# iv-17single.net
KiCad netlist of a schematic drawn in EAGLE
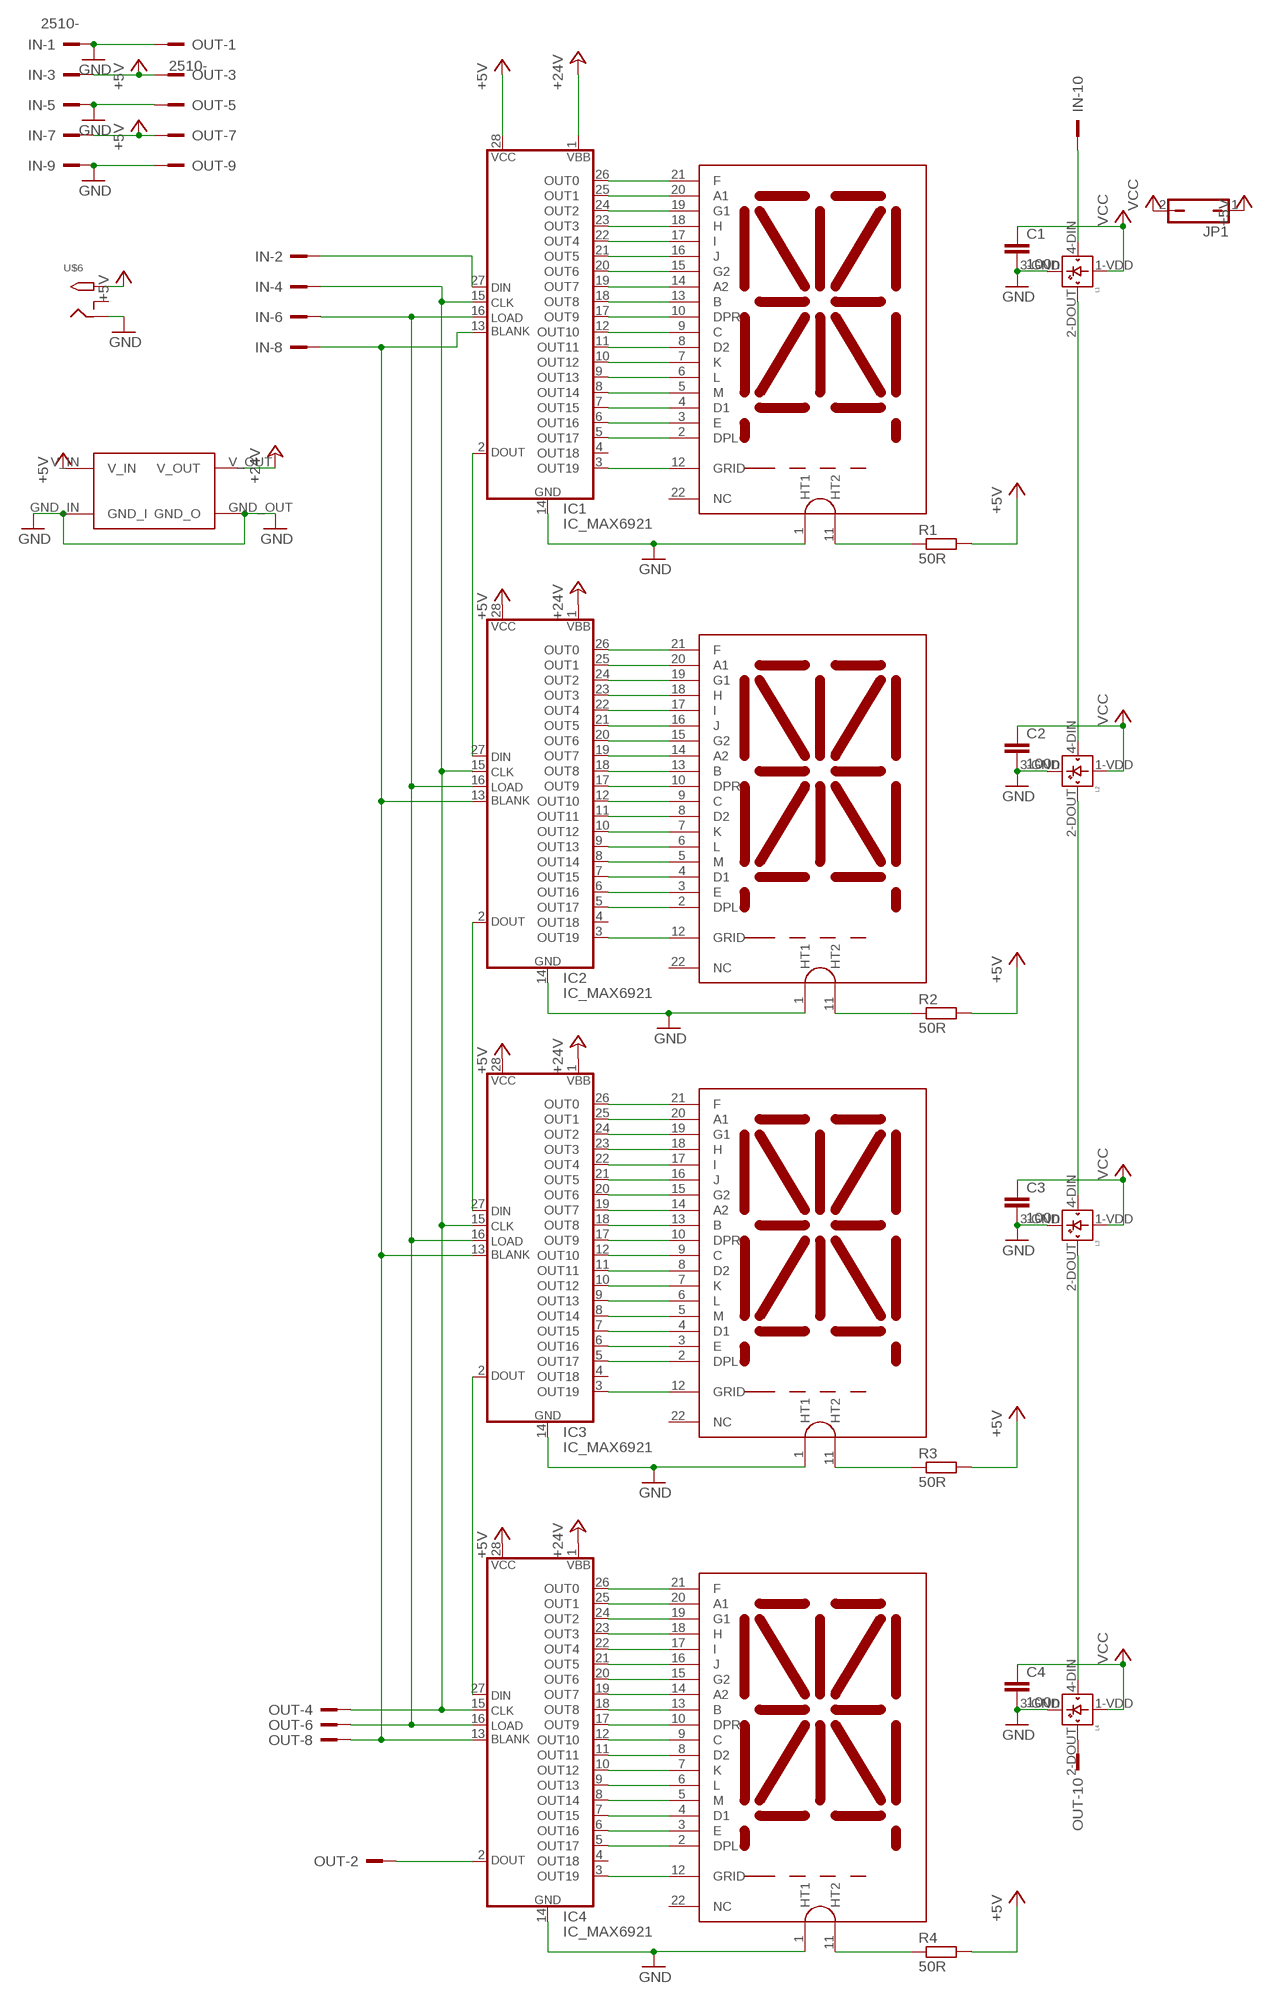
[diagram p0: schematic, sheet 1]

(export (version "E")
  (design (tool "Eeschema 10.0.6"))
  (components
    (comp (ref "1")
      (value "IV-17_DISPIV-17")
      (footprint "eagle-import:IV-17")
      (libsource (lib "eagle-import") (part "IV-17_DISPIV-17"))
    )
    (comp (ref "2")
      (value "IV-17_DISPIV-17")
      (footprint "eagle-import:IV-17")
      (libsource (lib "eagle-import") (part "IV-17_DISPIV-17"))
    )
    (comp (ref "3")
      (value "IV-17_DISPIV-17")
      (footprint "eagle-import:IV-17")
      (libsource (lib "eagle-import") (part "IV-17_DISPIV-17"))
    )
    (comp (ref "4")
      (value "IV-17_DISPIV-17")
      (footprint "eagle-import:IV-17")
      (libsource (lib "eagle-import") (part "IV-17_DISPIV-17"))
    )
    (comp (ref "C1")
      (value "100n")
      (footprint "eagle-import:C0805")
      (libsource (lib "eagle-import") (part "C-EUC0805"))
    )
    (comp (ref "C2")
      (value "100n")
      (footprint "eagle-import:C0805")
      (libsource (lib "eagle-import") (part "C-EUC0805"))
    )
    (comp (ref "C3")
      (value "100n")
      (footprint "eagle-import:C0805")
      (libsource (lib "eagle-import") (part "C-EUC0805"))
    )
    (comp (ref "C4")
      (value "100n")
      (footprint "eagle-import:C0805")
      (libsource (lib "eagle-import") (part "C-EUC0805"))
    )
    (comp (ref "IC1")
      (value "IC_MAX6921")
      (footprint "eagle-import:S28")
      (libsource (lib "eagle-import") (part "IC_MAX6921"))
    )
    (comp (ref "IC2")
      (value "IC_MAX6921")
      (footprint "eagle-import:S28")
      (libsource (lib "eagle-import") (part "IC_MAX6921"))
    )
    (comp (ref "IC3")
      (value "IC_MAX6921")
      (footprint "eagle-import:S28")
      (libsource (lib "eagle-import") (part "IC_MAX6921"))
    )
    (comp (ref "IC4")
      (value "IC_MAX6921")
      (footprint "eagle-import:S28")
      (libsource (lib "eagle-import") (part "IC_MAX6921"))
    )
    (comp (ref "IN")
      (value "2510-")
      (footprint "eagle-import:PAK100_2500-10")
      (fields (field (name "MF") "3M") (field (name "MPN") "2510-6002UB"))
      (libsource (lib "eagle-import") (part "2510-"))
    )
    (comp (ref "JP1")
      (value "JP1Q")
      (footprint "eagle-import:JP1")
      (libsource (lib "eagle-import") (part "JP1Q"))
    )
    (comp (ref "L1")
      (value "WS2812B")
      (footprint "eagle-import:WS2812B")
      (libsource (lib "eagle-import") (part "WS2812B"))
    )
    (comp (ref "L2")
      (value "WS2812B")
      (footprint "eagle-import:WS2812B")
      (libsource (lib "eagle-import") (part "WS2812B"))
    )
    (comp (ref "L3")
      (value "WS2812B")
      (footprint "eagle-import:WS2812B")
      (libsource (lib "eagle-import") (part "WS2812B"))
    )
    (comp (ref "L4")
      (value "WS2812B")
      (footprint "eagle-import:WS2812B")
      (libsource (lib "eagle-import") (part "WS2812B"))
    )
    (comp (ref "OUT")
      (value "2510-")
      (footprint "eagle-import:PAK100_2500-10")
      (fields (field (name "MF") "3M") (field (name "MPN") "2510-6002UB"))
      (libsource (lib "eagle-import") (part "2510-"))
    )
    (comp (ref "R1")
      (value "50R")
      (footprint "eagle-import:0207_10")
      (libsource (lib "eagle-import") (part "R-EU_0207/10"))
    )
    (comp (ref "R2")
      (value "50R")
      (footprint "eagle-import:0207_10")
      (libsource (lib "eagle-import") (part "R-EU_0207/10"))
    )
    (comp (ref "R3")
      (value "50R")
      (footprint "eagle-import:0207_10")
      (libsource (lib "eagle-import") (part "R-EU_0207/10"))
    )
    (comp (ref "R4")
      (value "50R")
      (footprint "eagle-import:0207_10")
      (libsource (lib "eagle-import") (part "R-EU_0207/10"))
    )
    (comp (ref "U$5")
      (value "STEP_UP_MODULE")
      (footprint "eagle-import:STEP_UP_MODULE")
      (libsource (lib "eagle-import") (part "STEP_UP_MODULE"))
    )
    (comp (ref "U$6")
      (value "2.1MMJACKTHM")
      (footprint "eagle-import:PJ-102A")
      (libsource (lib "eagle-import") (part "2.1MMJACKTHM"))
    )
  )
  (nets
    (net (code "1") (name "+5V") (class "Default")
      (node (ref "IC1") (pin "28") (pinfunction "VCC_28") (pintype "power_in"))
      (node (ref "IC2") (pin "28") (pinfunction "VCC_28") (pintype "power_in"))
      (node (ref "IC3") (pin "28") (pinfunction "VCC_28") (pintype "power_in"))
      (node (ref "IC4") (pin "28") (pinfunction "VCC_28") (pintype "power_in"))
      (node (ref "IN") (pin "3") (pinfunction "KL_3") (pintype "passive"))
      (node (ref "IN") (pin "7") (pinfunction "KL_7") (pintype "passive"))
      (node (ref "JP1") (pin "1") (pinfunction "1_1") (pintype "passive"))
      (node (ref "OUT") (pin "3") (pinfunction "KL_3") (pintype "passive"))
      (node (ref "OUT") (pin "7") (pinfunction "KL_7") (pintype "passive"))
      (node (ref "R1") (pin "2") (pinfunction "2_2") (pintype "passive"))
      (node (ref "R2") (pin "2") (pinfunction "2_2") (pintype "passive"))
      (node (ref "R3") (pin "2") (pinfunction "2_2") (pintype "passive"))
      (node (ref "R4") (pin "2") (pinfunction "2_2") (pintype "passive"))
      (node (ref "U$5") (pin "V_IN") (pinfunction "V_IN_V_IN") (pintype "power_in"))
      (node (ref "U$6") (pin "TIP") (pinfunction "TIP_TIP") (pintype "bidirectional"))
    )
    (net (code "2") (name "+24V") (class "Default")
      (node (ref "IC1") (pin "1") (pinfunction "VBB_1") (pintype "power_in"))
      (node (ref "IC2") (pin "1") (pinfunction "VBB_1") (pintype "power_in"))
      (node (ref "IC3") (pin "1") (pinfunction "VBB_1") (pintype "power_in"))
      (node (ref "IC4") (pin "1") (pinfunction "VBB_1") (pintype "power_in"))
      (node (ref "U$5") (pin "V_OUT") (pinfunction "V_OUT_V_OUT") (pintype "power_in"))
    )
    (net (code "3") (name "GND") (class "Default")
      (node (ref "1") (pin "1") (pinfunction "HT1_1") (pintype "power_in"))
      (node (ref "2") (pin "1") (pinfunction "HT1_1") (pintype "power_in"))
      (node (ref "3") (pin "1") (pinfunction "HT1_1") (pintype "power_in"))
      (node (ref "4") (pin "1") (pinfunction "HT1_1") (pintype "power_in"))
      (node (ref "C1") (pin "2") (pinfunction "2_2") (pintype "passive"))
      (node (ref "C2") (pin "2") (pinfunction "2_2") (pintype "passive"))
      (node (ref "C3") (pin "2") (pinfunction "2_2") (pintype "passive"))
      (node (ref "C4") (pin "2") (pinfunction "2_2") (pintype "passive"))
      (node (ref "IC1") (pin "14") (pinfunction "GND_14") (pintype "power_in"))
      (node (ref "IC2") (pin "14") (pinfunction "GND_14") (pintype "power_in"))
      (node (ref "IC3") (pin "14") (pinfunction "GND_14") (pintype "power_in"))
      (node (ref "IC4") (pin "14") (pinfunction "GND_14") (pintype "power_in"))
      (node (ref "IN") (pin "1") (pinfunction "KL_1") (pintype "passive"))
      (node (ref "IN") (pin "5") (pinfunction "KL_5") (pintype "passive"))
      (node (ref "IN") (pin "9") (pinfunction "KL_9") (pintype "passive"))
      (node (ref "L1") (pin "3-GND") (pinfunction "GND_3-GND") (pintype "bidirectional"))
      (node (ref "L2") (pin "3-GND") (pinfunction "GND_3-GND") (pintype "bidirectional"))
      (node (ref "L3") (pin "3-GND") (pinfunction "GND_3-GND") (pintype "bidirectional"))
      (node (ref "L4") (pin "3-GND") (pinfunction "GND_3-GND") (pintype "bidirectional"))
      (node (ref "OUT") (pin "1") (pinfunction "KL_1") (pintype "passive"))
      (node (ref "OUT") (pin "5") (pinfunction "KL_5") (pintype "passive"))
      (node (ref "OUT") (pin "9") (pinfunction "KL_9") (pintype "passive"))
      (node (ref "U$5") (pin "GND_IN") (pinfunction "GND_I_GND_IN") (pintype "power_in"))
      (node (ref "U$5") (pin "GND_OUT") (pinfunction "GND_O_GND_OUT") (pintype "power_in"))
      (node (ref "U$6") (pin "RING") (pinfunction "RING_RING") (pintype "bidirectional"))
    )
    (net (code "4") (name "Net-(1-A1)") (class "Default")
      (node (ref "1") (pin "20") (pinfunction "A1_20") (pintype "input"))
      (node (ref "IC1") (pin "25") (pinfunction "OUT1_25") (pintype "output"))
    )
    (net (code "5") (name "Net-(1-A2)") (class "Default")
      (node (ref "1") (pin "14") (pinfunction "A2_14") (pintype "input"))
      (node (ref "IC1") (pin "19") (pinfunction "OUT7_19") (pintype "output"))
    )
    (net (code "6") (name "Net-(1-B)") (class "Default")
      (node (ref "1") (pin "13") (pinfunction "B_13") (pintype "input"))
      (node (ref "IC1") (pin "18") (pinfunction "OUT8_18") (pintype "output"))
    )
    (net (code "7") (name "Net-(1-C)") (class "Default")
      (node (ref "1") (pin "9") (pinfunction "C_9") (pintype "input"))
      (node (ref "IC1") (pin "12") (pinfunction "OUT10_12") (pintype "output"))
    )
    (net (code "8") (name "Net-(1-D1)") (class "Default")
      (node (ref "1") (pin "4") (pinfunction "D1_4") (pintype "input"))
      (node (ref "IC1") (pin "7") (pinfunction "OUT15_7") (pintype "output"))
    )
    (net (code "9") (name "Net-(1-D2)") (class "Default")
      (node (ref "1") (pin "8") (pinfunction "D2_8") (pintype "input"))
      (node (ref "IC1") (pin "11") (pinfunction "OUT11_11") (pintype "output"))
    )
    (net (code "10") (name "Net-(1-DPL)") (class "Default")
      (node (ref "1") (pin "2") (pinfunction "DPL_2") (pintype "input"))
      (node (ref "IC1") (pin "5") (pinfunction "OUT17_5") (pintype "output"))
    )
    (net (code "11") (name "Net-(1-DPR)") (class "Default")
      (node (ref "1") (pin "10") (pinfunction "DPR_10") (pintype "input"))
      (node (ref "IC1") (pin "17") (pinfunction "OUT9_17") (pintype "output"))
    )
    (net (code "12") (name "Net-(1-E)") (class "Default")
      (node (ref "1") (pin "3") (pinfunction "E_3") (pintype "input"))
      (node (ref "IC1") (pin "6") (pinfunction "OUT16_6") (pintype "output"))
    )
    (net (code "13") (name "Net-(1-F)") (class "Default")
      (node (ref "1") (pin "21") (pinfunction "F_21") (pintype "input"))
      (node (ref "IC1") (pin "26") (pinfunction "OUT0_26") (pintype "output"))
    )
    (net (code "14") (name "Net-(1-G1)") (class "Default")
      (node (ref "1") (pin "19") (pinfunction "G1_19") (pintype "input"))
      (node (ref "IC1") (pin "24") (pinfunction "OUT2_24") (pintype "output"))
    )
    (net (code "15") (name "Net-(1-G2)") (class "Default")
      (node (ref "1") (pin "15") (pinfunction "G2_15") (pintype "input"))
      (node (ref "IC1") (pin "20") (pinfunction "OUT6_20") (pintype "output"))
    )
    (net (code "16") (name "Net-(1-GRID)") (class "Default")
      (node (ref "1") (pin "12") (pinfunction "GRID_12") (pintype "input"))
      (node (ref "IC1") (pin "3") (pinfunction "OUT19_3") (pintype "output"))
    )
    (net (code "17") (name "Net-(1-H)") (class "Default")
      (node (ref "1") (pin "18") (pinfunction "H_18") (pintype "input"))
      (node (ref "IC1") (pin "23") (pinfunction "OUT3_23") (pintype "output"))
    )
    (net (code "18") (name "Net-(1-HT2)") (class "Default")
      (node (ref "1") (pin "11") (pinfunction "HT2_11") (pintype "power_in"))
      (node (ref "R1") (pin "1") (pinfunction "1_1") (pintype "passive"))
    )
    (net (code "19") (name "Net-(1-I)") (class "Default")
      (node (ref "1") (pin "17") (pinfunction "I_17") (pintype "input"))
      (node (ref "IC1") (pin "22") (pinfunction "OUT4_22") (pintype "output"))
    )
    (net (code "20") (name "Net-(1-J)") (class "Default")
      (node (ref "1") (pin "16") (pinfunction "J_16") (pintype "input"))
      (node (ref "IC1") (pin "21") (pinfunction "OUT5_21") (pintype "output"))
    )
    (net (code "21") (name "Net-(1-K)") (class "Default")
      (node (ref "1") (pin "7") (pinfunction "K_7") (pintype "input"))
      (node (ref "IC1") (pin "10") (pinfunction "OUT12_10") (pintype "output"))
    )
    (net (code "22") (name "Net-(1-L)") (class "Default")
      (node (ref "1") (pin "6") (pinfunction "L_6") (pintype "input"))
      (node (ref "IC1") (pin "9") (pinfunction "OUT13_9") (pintype "output"))
    )
    (net (code "23") (name "Net-(1-M)") (class "Default")
      (node (ref "1") (pin "5") (pinfunction "M_5") (pintype "input"))
      (node (ref "IC1") (pin "8") (pinfunction "OUT14_8") (pintype "output"))
    )
    (net (code "24") (name "Net-(2-A1)") (class "Default")
      (node (ref "2") (pin "20") (pinfunction "A1_20") (pintype "input"))
      (node (ref "IC2") (pin "25") (pinfunction "OUT1_25") (pintype "output"))
    )
    (net (code "25") (name "Net-(2-A2)") (class "Default")
      (node (ref "2") (pin "14") (pinfunction "A2_14") (pintype "input"))
      (node (ref "IC2") (pin "19") (pinfunction "OUT7_19") (pintype "output"))
    )
    (net (code "26") (name "Net-(2-B)") (class "Default")
      (node (ref "2") (pin "13") (pinfunction "B_13") (pintype "input"))
      (node (ref "IC2") (pin "18") (pinfunction "OUT8_18") (pintype "output"))
    )
    (net (code "27") (name "Net-(2-C)") (class "Default")
      (node (ref "2") (pin "9") (pinfunction "C_9") (pintype "input"))
      (node (ref "IC2") (pin "12") (pinfunction "OUT10_12") (pintype "output"))
    )
    (net (code "28") (name "Net-(2-D1)") (class "Default")
      (node (ref "2") (pin "4") (pinfunction "D1_4") (pintype "input"))
      (node (ref "IC2") (pin "7") (pinfunction "OUT15_7") (pintype "output"))
    )
    (net (code "29") (name "Net-(2-D2)") (class "Default")
      (node (ref "2") (pin "8") (pinfunction "D2_8") (pintype "input"))
      (node (ref "IC2") (pin "11") (pinfunction "OUT11_11") (pintype "output"))
    )
    (net (code "30") (name "Net-(2-DPL)") (class "Default")
      (node (ref "2") (pin "2") (pinfunction "DPL_2") (pintype "input"))
      (node (ref "IC2") (pin "5") (pinfunction "OUT17_5") (pintype "output"))
    )
    (net (code "31") (name "Net-(2-DPR)") (class "Default")
      (node (ref "2") (pin "10") (pinfunction "DPR_10") (pintype "input"))
      (node (ref "IC2") (pin "17") (pinfunction "OUT9_17") (pintype "output"))
    )
    (net (code "32") (name "Net-(2-E)") (class "Default")
      (node (ref "2") (pin "3") (pinfunction "E_3") (pintype "input"))
      (node (ref "IC2") (pin "6") (pinfunction "OUT16_6") (pintype "output"))
    )
    (net (code "33") (name "Net-(2-F)") (class "Default")
      (node (ref "2") (pin "21") (pinfunction "F_21") (pintype "input"))
      (node (ref "IC2") (pin "26") (pinfunction "OUT0_26") (pintype "output"))
    )
    (net (code "34") (name "Net-(2-G1)") (class "Default")
      (node (ref "2") (pin "19") (pinfunction "G1_19") (pintype "input"))
      (node (ref "IC2") (pin "24") (pinfunction "OUT2_24") (pintype "output"))
    )
    (net (code "35") (name "Net-(2-G2)") (class "Default")
      (node (ref "2") (pin "15") (pinfunction "G2_15") (pintype "input"))
      (node (ref "IC2") (pin "20") (pinfunction "OUT6_20") (pintype "output"))
    )
    (net (code "36") (name "Net-(2-GRID)") (class "Default")
      (node (ref "2") (pin "12") (pinfunction "GRID_12") (pintype "input"))
      (node (ref "IC2") (pin "3") (pinfunction "OUT19_3") (pintype "output"))
    )
    (net (code "37") (name "Net-(2-H)") (class "Default")
      (node (ref "2") (pin "18") (pinfunction "H_18") (pintype "input"))
      (node (ref "IC2") (pin "23") (pinfunction "OUT3_23") (pintype "output"))
    )
    (net (code "38") (name "Net-(2-HT2)") (class "Default")
      (node (ref "2") (pin "11") (pinfunction "HT2_11") (pintype "power_in"))
      (node (ref "R2") (pin "1") (pinfunction "1_1") (pintype "passive"))
    )
    (net (code "39") (name "Net-(2-I)") (class "Default")
      (node (ref "2") (pin "17") (pinfunction "I_17") (pintype "input"))
      (node (ref "IC2") (pin "22") (pinfunction "OUT4_22") (pintype "output"))
    )
    (net (code "40") (name "Net-(2-J)") (class "Default")
      (node (ref "2") (pin "16") (pinfunction "J_16") (pintype "input"))
      (node (ref "IC2") (pin "21") (pinfunction "OUT5_21") (pintype "output"))
    )
    (net (code "41") (name "Net-(2-K)") (class "Default")
      (node (ref "2") (pin "7") (pinfunction "K_7") (pintype "input"))
      (node (ref "IC2") (pin "10") (pinfunction "OUT12_10") (pintype "output"))
    )
    (net (code "42") (name "Net-(2-L)") (class "Default")
      (node (ref "2") (pin "6") (pinfunction "L_6") (pintype "input"))
      (node (ref "IC2") (pin "9") (pinfunction "OUT13_9") (pintype "output"))
    )
    (net (code "43") (name "Net-(2-M)") (class "Default")
      (node (ref "2") (pin "5") (pinfunction "M_5") (pintype "input"))
      (node (ref "IC2") (pin "8") (pinfunction "OUT14_8") (pintype "output"))
    )
    (net (code "44") (name "Net-(3-A1)") (class "Default")
      (node (ref "3") (pin "20") (pinfunction "A1_20") (pintype "input"))
      (node (ref "IC3") (pin "25") (pinfunction "OUT1_25") (pintype "output"))
    )
    (net (code "45") (name "Net-(3-A2)") (class "Default")
      (node (ref "3") (pin "14") (pinfunction "A2_14") (pintype "input"))
      (node (ref "IC3") (pin "19") (pinfunction "OUT7_19") (pintype "output"))
    )
    (net (code "46") (name "Net-(3-B)") (class "Default")
      (node (ref "3") (pin "13") (pinfunction "B_13") (pintype "input"))
      (node (ref "IC3") (pin "18") (pinfunction "OUT8_18") (pintype "output"))
    )
    (net (code "47") (name "Net-(3-C)") (class "Default")
      (node (ref "3") (pin "9") (pinfunction "C_9") (pintype "input"))
      (node (ref "IC3") (pin "12") (pinfunction "OUT10_12") (pintype "output"))
    )
    (net (code "48") (name "Net-(3-D1)") (class "Default")
      (node (ref "3") (pin "4") (pinfunction "D1_4") (pintype "input"))
      (node (ref "IC3") (pin "7") (pinfunction "OUT15_7") (pintype "output"))
    )
    (net (code "49") (name "Net-(3-D2)") (class "Default")
      (node (ref "3") (pin "8") (pinfunction "D2_8") (pintype "input"))
      (node (ref "IC3") (pin "11") (pinfunction "OUT11_11") (pintype "output"))
    )
    (net (code "50") (name "Net-(3-DPL)") (class "Default")
      (node (ref "3") (pin "2") (pinfunction "DPL_2") (pintype "input"))
      (node (ref "IC3") (pin "5") (pinfunction "OUT17_5") (pintype "output"))
    )
    (net (code "51") (name "Net-(3-DPR)") (class "Default")
      (node (ref "3") (pin "10") (pinfunction "DPR_10") (pintype "input"))
      (node (ref "IC3") (pin "17") (pinfunction "OUT9_17") (pintype "output"))
    )
    (net (code "52") (name "Net-(3-E)") (class "Default")
      (node (ref "3") (pin "3") (pinfunction "E_3") (pintype "input"))
      (node (ref "IC3") (pin "6") (pinfunction "OUT16_6") (pintype "output"))
    )
    (net (code "53") (name "Net-(3-F)") (class "Default")
      (node (ref "3") (pin "21") (pinfunction "F_21") (pintype "input"))
      (node (ref "IC3") (pin "26") (pinfunction "OUT0_26") (pintype "output"))
    )
    (net (code "54") (name "Net-(3-G1)") (class "Default")
      (node (ref "3") (pin "19") (pinfunction "G1_19") (pintype "input"))
      (node (ref "IC3") (pin "24") (pinfunction "OUT2_24") (pintype "output"))
    )
    (net (code "55") (name "Net-(3-G2)") (class "Default")
      (node (ref "3") (pin "15") (pinfunction "G2_15") (pintype "input"))
      (node (ref "IC3") (pin "20") (pinfunction "OUT6_20") (pintype "output"))
    )
    (net (code "56") (name "Net-(3-GRID)") (class "Default")
      (node (ref "3") (pin "12") (pinfunction "GRID_12") (pintype "input"))
      (node (ref "IC3") (pin "3") (pinfunction "OUT19_3") (pintype "output"))
    )
    (net (code "57") (name "Net-(3-H)") (class "Default")
      (node (ref "3") (pin "18") (pinfunction "H_18") (pintype "input"))
      (node (ref "IC3") (pin "23") (pinfunction "OUT3_23") (pintype "output"))
    )
    (net (code "58") (name "Net-(3-HT2)") (class "Default")
      (node (ref "3") (pin "11") (pinfunction "HT2_11") (pintype "power_in"))
      (node (ref "R3") (pin "1") (pinfunction "1_1") (pintype "passive"))
    )
    (net (code "59") (name "Net-(3-I)") (class "Default")
      (node (ref "3") (pin "17") (pinfunction "I_17") (pintype "input"))
      (node (ref "IC3") (pin "22") (pinfunction "OUT4_22") (pintype "output"))
    )
    (net (code "60") (name "Net-(3-J)") (class "Default")
      (node (ref "3") (pin "16") (pinfunction "J_16") (pintype "input"))
      (node (ref "IC3") (pin "21") (pinfunction "OUT5_21") (pintype "output"))
    )
    (net (code "61") (name "Net-(3-K)") (class "Default")
      (node (ref "3") (pin "7") (pinfunction "K_7") (pintype "input"))
      (node (ref "IC3") (pin "10") (pinfunction "OUT12_10") (pintype "output"))
    )
    (net (code "62") (name "Net-(3-L)") (class "Default")
      (node (ref "3") (pin "6") (pinfunction "L_6") (pintype "input"))
      (node (ref "IC3") (pin "9") (pinfunction "OUT13_9") (pintype "output"))
    )
    (net (code "63") (name "Net-(3-M)") (class "Default")
      (node (ref "3") (pin "5") (pinfunction "M_5") (pintype "input"))
      (node (ref "IC3") (pin "8") (pinfunction "OUT14_8") (pintype "output"))
    )
    (net (code "64") (name "Net-(4-A1)") (class "Default")
      (node (ref "4") (pin "20") (pinfunction "A1_20") (pintype "input"))
      (node (ref "IC4") (pin "25") (pinfunction "OUT1_25") (pintype "output"))
    )
    (net (code "65") (name "Net-(4-A2)") (class "Default")
      (node (ref "4") (pin "14") (pinfunction "A2_14") (pintype "input"))
      (node (ref "IC4") (pin "19") (pinfunction "OUT7_19") (pintype "output"))
    )
    (net (code "66") (name "Net-(4-B)") (class "Default")
      (node (ref "4") (pin "13") (pinfunction "B_13") (pintype "input"))
      (node (ref "IC4") (pin "18") (pinfunction "OUT8_18") (pintype "output"))
    )
    (net (code "67") (name "Net-(4-C)") (class "Default")
      (node (ref "4") (pin "9") (pinfunction "C_9") (pintype "input"))
      (node (ref "IC4") (pin "12") (pinfunction "OUT10_12") (pintype "output"))
    )
    (net (code "68") (name "Net-(4-D1)") (class "Default")
      (node (ref "4") (pin "4") (pinfunction "D1_4") (pintype "input"))
      (node (ref "IC4") (pin "7") (pinfunction "OUT15_7") (pintype "output"))
    )
    (net (code "69") (name "Net-(4-D2)") (class "Default")
      (node (ref "4") (pin "8") (pinfunction "D2_8") (pintype "input"))
      (node (ref "IC4") (pin "11") (pinfunction "OUT11_11") (pintype "output"))
    )
    (net (code "70") (name "Net-(4-DPL)") (class "Default")
      (node (ref "4") (pin "2") (pinfunction "DPL_2") (pintype "input"))
      (node (ref "IC4") (pin "5") (pinfunction "OUT17_5") (pintype "output"))
    )
    (net (code "71") (name "Net-(4-DPR)") (class "Default")
      (node (ref "4") (pin "10") (pinfunction "DPR_10") (pintype "input"))
      (node (ref "IC4") (pin "17") (pinfunction "OUT9_17") (pintype "output"))
    )
    (net (code "72") (name "Net-(4-E)") (class "Default")
      (node (ref "4") (pin "3") (pinfunction "E_3") (pintype "input"))
      (node (ref "IC4") (pin "6") (pinfunction "OUT16_6") (pintype "output"))
    )
    (net (code "73") (name "Net-(4-F)") (class "Default")
      (node (ref "4") (pin "21") (pinfunction "F_21") (pintype "input"))
      (node (ref "IC4") (pin "26") (pinfunction "OUT0_26") (pintype "output"))
    )
    (net (code "74") (name "Net-(4-G1)") (class "Default")
      (node (ref "4") (pin "19") (pinfunction "G1_19") (pintype "input"))
      (node (ref "IC4") (pin "24") (pinfunction "OUT2_24") (pintype "output"))
    )
    (net (code "75") (name "Net-(4-G2)") (class "Default")
      (node (ref "4") (pin "15") (pinfunction "G2_15") (pintype "input"))
      (node (ref "IC4") (pin "20") (pinfunction "OUT6_20") (pintype "output"))
    )
    (net (code "76") (name "Net-(4-GRID)") (class "Default")
      (node (ref "4") (pin "12") (pinfunction "GRID_12") (pintype "input"))
      (node (ref "IC4") (pin "3") (pinfunction "OUT19_3") (pintype "output"))
    )
    (net (code "77") (name "Net-(4-H)") (class "Default")
      (node (ref "4") (pin "18") (pinfunction "H_18") (pintype "input"))
      (node (ref "IC4") (pin "23") (pinfunction "OUT3_23") (pintype "output"))
    )
    (net (code "78") (name "Net-(4-HT2)") (class "Default")
      (node (ref "4") (pin "11") (pinfunction "HT2_11") (pintype "power_in"))
      (node (ref "R4") (pin "1") (pinfunction "1_1") (pintype "passive"))
    )
    (net (code "79") (name "Net-(4-I)") (class "Default")
      (node (ref "4") (pin "17") (pinfunction "I_17") (pintype "input"))
      (node (ref "IC4") (pin "22") (pinfunction "OUT4_22") (pintype "output"))
    )
    (net (code "80") (name "Net-(4-J)") (class "Default")
      (node (ref "4") (pin "16") (pinfunction "J_16") (pintype "input"))
      (node (ref "IC4") (pin "21") (pinfunction "OUT5_21") (pintype "output"))
    )
    (net (code "81") (name "Net-(4-K)") (class "Default")
      (node (ref "4") (pin "7") (pinfunction "K_7") (pintype "input"))
      (node (ref "IC4") (pin "10") (pinfunction "OUT12_10") (pintype "output"))
    )
    (net (code "82") (name "Net-(4-L)") (class "Default")
      (node (ref "4") (pin "6") (pinfunction "L_6") (pintype "input"))
      (node (ref "IC4") (pin "9") (pinfunction "OUT13_9") (pintype "output"))
    )
    (net (code "83") (name "Net-(4-M)") (class "Default")
      (node (ref "4") (pin "5") (pinfunction "M_5") (pintype "input"))
      (node (ref "IC4") (pin "8") (pinfunction "OUT14_8") (pintype "output"))
    )
    (net (code "84") (name "Net-(IC1-BLANK)") (class "Default")
      (node (ref "IC1") (pin "13") (pinfunction "BLANK_13") (pintype "input"))
      (node (ref "IC2") (pin "13") (pinfunction "BLANK_13") (pintype "input"))
      (node (ref "IC3") (pin "13") (pinfunction "BLANK_13") (pintype "input"))
      (node (ref "IC4") (pin "13") (pinfunction "BLANK_13") (pintype "input"))
      (node (ref "IN") (pin "8") (pinfunction "KL_8") (pintype "passive"))
      (node (ref "OUT") (pin "8") (pinfunction "KL_8") (pintype "passive"))
    )
    (net (code "85") (name "Net-(IC1-CLK)") (class "Default")
      (node (ref "IC1") (pin "15") (pinfunction "CLK_15") (pintype "input"))
      (node (ref "IC2") (pin "15") (pinfunction "CLK_15") (pintype "input"))
      (node (ref "IC3") (pin "15") (pinfunction "CLK_15") (pintype "input"))
      (node (ref "IC4") (pin "15") (pinfunction "CLK_15") (pintype "input"))
      (node (ref "IN") (pin "4") (pinfunction "KL_4") (pintype "passive"))
      (node (ref "OUT") (pin "4") (pinfunction "KL_4") (pintype "passive"))
    )
    (net (code "86") (name "Net-(IC1-DIN)") (class "Default")
      (node (ref "IC1") (pin "27") (pinfunction "DIN_27") (pintype "input"))
      (node (ref "IN") (pin "2") (pinfunction "KL_2") (pintype "passive"))
    )
    (net (code "87") (name "Net-(IC1-DOUT)") (class "Default")
      (node (ref "IC1") (pin "2") (pinfunction "DOUT_2") (pintype "output"))
      (node (ref "IC2") (pin "27") (pinfunction "DIN_27") (pintype "input"))
    )
    (net (code "88") (name "Net-(IC1-LOAD)") (class "Default")
      (node (ref "IC1") (pin "16") (pinfunction "LOAD_16") (pintype "input"))
      (node (ref "IC2") (pin "16") (pinfunction "LOAD_16") (pintype "input"))
      (node (ref "IC3") (pin "16") (pinfunction "LOAD_16") (pintype "input"))
      (node (ref "IC4") (pin "16") (pinfunction "LOAD_16") (pintype "input"))
      (node (ref "IN") (pin "6") (pinfunction "KL_6") (pintype "passive"))
      (node (ref "OUT") (pin "6") (pinfunction "KL_6") (pintype "passive"))
    )
    (net (code "89") (name "Net-(IC2-DOUT)") (class "Default")
      (node (ref "IC2") (pin "2") (pinfunction "DOUT_2") (pintype "output"))
      (node (ref "IC3") (pin "27") (pinfunction "DIN_27") (pintype "input"))
    )
    (net (code "90") (name "Net-(IC3-DOUT)") (class "Default")
      (node (ref "IC3") (pin "2") (pinfunction "DOUT_2") (pintype "output"))
      (node (ref "IC4") (pin "27") (pinfunction "DIN_27") (pintype "input"))
    )
    (net (code "91") (name "Net-(IC4-DOUT)") (class "Default")
      (node (ref "IC4") (pin "2") (pinfunction "DOUT_2") (pintype "output"))
      (node (ref "OUT") (pin "2") (pinfunction "KL_2") (pintype "passive"))
    )
    (net (code "92") (name "Net-(INB-KL)") (class "Default")
      (node (ref "IN") (pin "10") (pinfunction "KL_10") (pintype "passive"))
      (node (ref "L1") (pin "4-DIN") (pinfunction "DIN_4-DIN") (pintype "input"))
    )
    (net (code "93") (name "Net-(L1-DOUT)") (class "Default")
      (node (ref "L1") (pin "2-DOUT") (pinfunction "DOUT_2-DOUT") (pintype "output"))
      (node (ref "L2") (pin "4-DIN") (pinfunction "DIN_4-DIN") (pintype "input"))
    )
    (net (code "94") (name "Net-(L2-DOUT)") (class "Default")
      (node (ref "L2") (pin "2-DOUT") (pinfunction "DOUT_2-DOUT") (pintype "output"))
      (node (ref "L3") (pin "4-DIN") (pinfunction "DIN_4-DIN") (pintype "input"))
    )
    (net (code "95") (name "Net-(L3-DOUT)") (class "Default")
      (node (ref "L3") (pin "2-DOUT") (pinfunction "DOUT_2-DOUT") (pintype "output"))
      (node (ref "L4") (pin "4-DIN") (pinfunction "DIN_4-DIN") (pintype "input"))
    )
    (net (code "96") (name "Net-(L4-DOUT)") (class "Default")
      (node (ref "L4") (pin "2-DOUT") (pinfunction "DOUT_2-DOUT") (pintype "output"))
      (node (ref "OUT") (pin "10") (pinfunction "KL_10") (pintype "passive"))
    )
    (net (code "97") (name "VCC") (class "Default")
      (node (ref "C1") (pin "1") (pinfunction "1_1") (pintype "passive"))
      (node (ref "C2") (pin "1") (pinfunction "1_1") (pintype "passive"))
      (node (ref "C3") (pin "1") (pinfunction "1_1") (pintype "passive"))
      (node (ref "C4") (pin "1") (pinfunction "1_1") (pintype "passive"))
      (node (ref "JP1") (pin "2") (pinfunction "2_2") (pintype "passive"))
      (node (ref "L1") (pin "1-VDD") (pinfunction "VDD_1-VDD") (pintype "bidirectional"))
      (node (ref "L2") (pin "1-VDD") (pinfunction "VDD_1-VDD") (pintype "bidirectional"))
      (node (ref "L3") (pin "1-VDD") (pinfunction "VDD_1-VDD") (pintype "bidirectional"))
      (node (ref "L4") (pin "1-VDD") (pinfunction "VDD_1-VDD") (pintype "bidirectional"))
    )
    (net (code "98") (name "unconnected-(1-NC-Pad22)") (class "Default")
      (node (ref "1") (pin "22") (pinfunction "NC_22") (pintype "no_connect"))
    )
    (net (code "99") (name "unconnected-(2-NC-Pad22)") (class "Default")
      (node (ref "2") (pin "22") (pinfunction "NC_22") (pintype "no_connect"))
    )
    (net (code "100") (name "unconnected-(3-NC-Pad22)") (class "Default")
      (node (ref "3") (pin "22") (pinfunction "NC_22") (pintype "no_connect"))
    )
    (net (code "101") (name "unconnected-(4-NC-Pad22)") (class "Default")
      (node (ref "4") (pin "22") (pinfunction "NC_22") (pintype "no_connect"))
    )
    (net (code "102") (name "unconnected-(IC1-OUT18-Pad4)") (class "Default")
      (node (ref "IC1") (pin "4") (pinfunction "OUT18_4") (pintype "output"))
    )
    (net (code "103") (name "unconnected-(IC2-OUT18-Pad4)") (class "Default")
      (node (ref "IC2") (pin "4") (pinfunction "OUT18_4") (pintype "output"))
    )
    (net (code "104") (name "unconnected-(IC3-OUT18-Pad4)") (class "Default")
      (node (ref "IC3") (pin "4") (pinfunction "OUT18_4") (pintype "output"))
    )
    (net (code "105") (name "unconnected-(IC4-OUT18-Pad4)") (class "Default")
      (node (ref "IC4") (pin "4") (pinfunction "OUT18_4") (pintype "output"))
    )
    (net (code "106") (name "unconnected-(U$6-PadRING_SW)") (class "Default")
      (node (ref "U$6") (pin "RING_SW") (pinfunction "RING_SW_RING_SW") (pintype "bidirectional"))
    )
  )
)
